# TIDA-010933-DCDC-Boost.net
KiCad netlist of a schematic drawn in Altium Designer
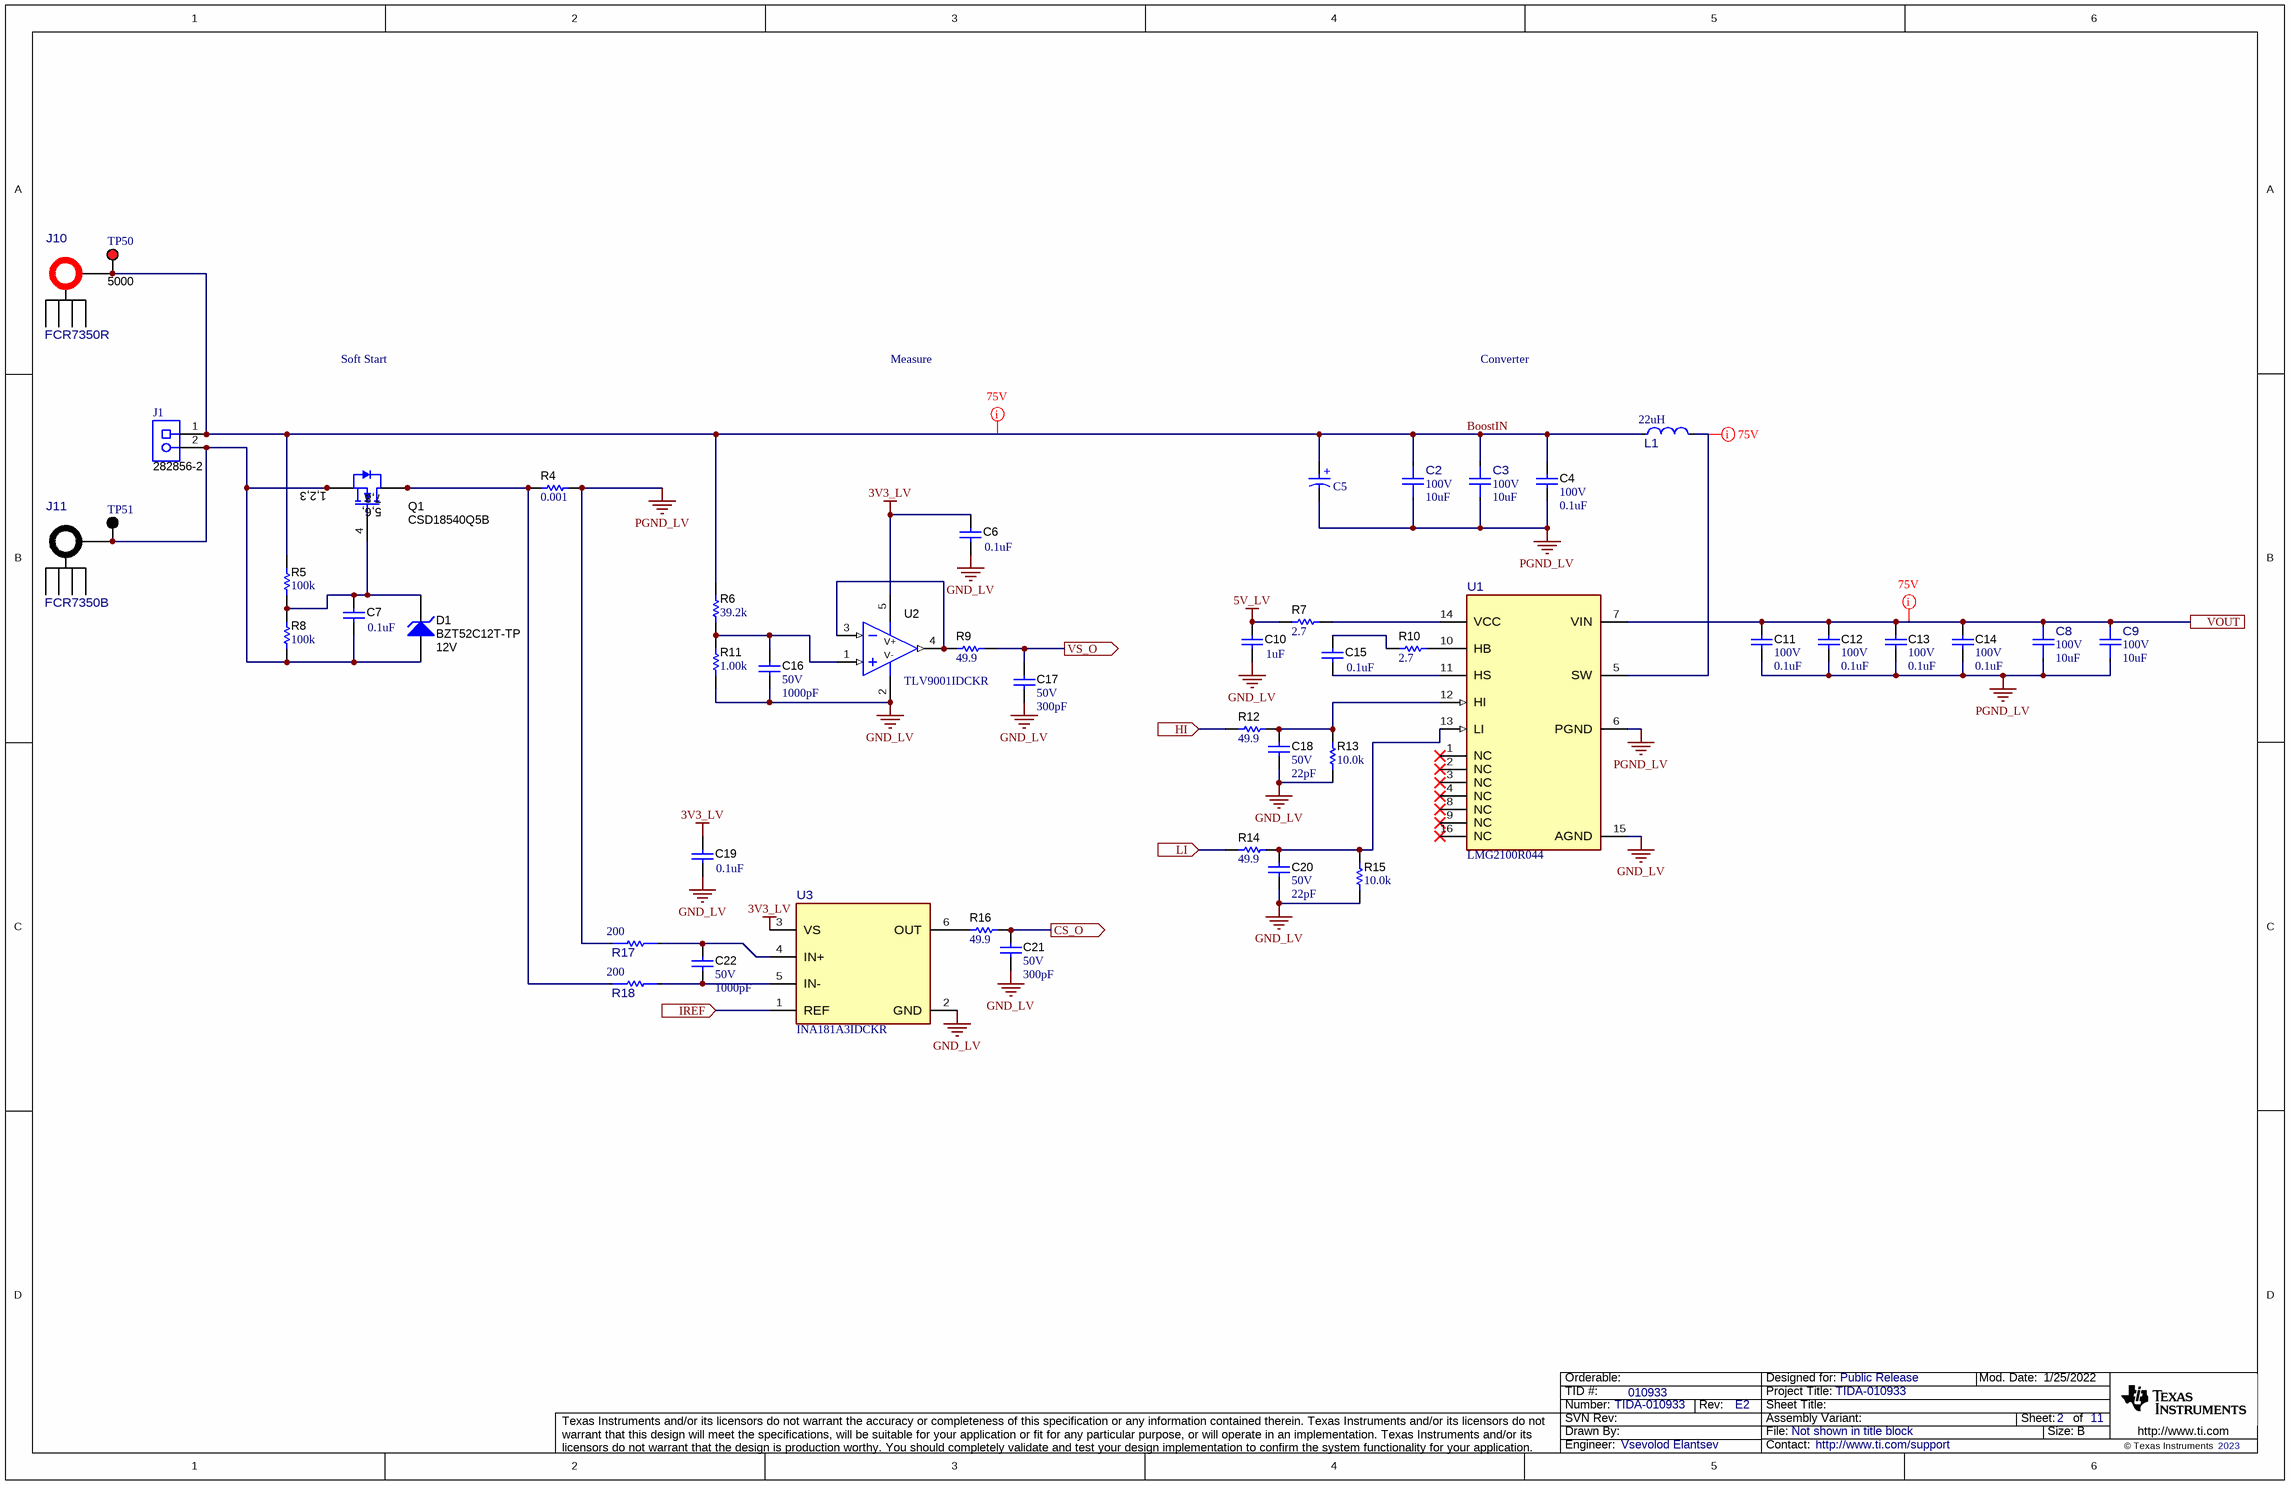
[diagram p0: TIDA-010933-DCDC-Boost.SchDoc]

(export (version "E")
  (design (tool "Eeschema 10.0.6"))
  (components
    (comp (ref "C2")
      (value "C3225X7R2A106K250AC")
      (footprint "FP-C3225X7R2A106K250AC_1210-MFG")
      (description "10 µF ±10% 100V Ceramic Capacitor X7R 1210 (3225 Metric)")
      (fields
        (field (name "DIGIKEY PART NUMBER") "445-C3225X7R2A106K250ACCT-ND")
        (field (name "MOUSER PART NUMBER") "810-C3225X7R2A106K25")
        (field (name "VDC_V") "100V")
        (field (name "VALUEDISPLAYED") "10uF")
      )
      (libsource (lib "Altium Vault - TI") (part "SYM-C3225X7R2A106K250AC"))
    )
    (comp (ref "C3")
      (value "C3225X7R2A106K250AC")
      (footprint "FP-C3225X7R2A106K250AC_1210-MFG")
      (description "10 µF ±10% 100V Ceramic Capacitor X7R 1210 (3225 Metric)")
      (fields
        (field (name "DIGIKEY PART NUMBER") "445-C3225X7R2A106K250ACCT-ND")
        (field (name "MOUSER PART NUMBER") "810-C3225X7R2A106K25")
        (field (name "VDC_V") "100V")
        (field (name "VALUEDISPLAYED") "10uF")
      )
      (libsource (lib "Altium Vault - TI") (part "SYM-C3225X7R2A106K250AC"))
    )
    (comp (ref "C4")
      (value "GRM155R62A104KE14D")
      (footprint "0402")
      (description "CAP, CERM, 0.1 uF, 100 V, +/- 10%, X5R, 0402")
      (fields
        (field (name "MANUFACTURER") "MuRata")
        (field (name "VDC_V") "100V")
        (field (name "VALUEDISPLAYED") "0.1uF")
        (field (name "PUBLISHER") "Texas Instruments")
      )
      (libsource (lib "Altium Vault - TI") (part "Capacitor"))
    )
    (comp (ref "C5")
      (value "860080775016")
      (footprint "WCAP-ATLI_D10H16")
      (description "WCAP-ATLI Aluminum Electrolytic Capacitor, Radial, THT, D10 x H16mm, 150µF, 63V")
      (fields (field (name "MANUFACTURER") "Wurth Elektronik"))
      (libsource (lib "Altium Vault - TI") (part "875585961005"))
    )
    (comp (ref "C6")
      (value "GRM155R71E104KE14D")
      (footprint "0402")
      (description "CAP, CERM, 0.1 uF, 25 V, +/- 10%, X7R, 0402")
      (fields
        (field (name "MANUFACTURER") "MuRata")
        (field (name "VALUEDISPLAYED") "0.1uF")
        (field (name "PUBLISHER") "Texas Instruments")
      )
      (libsource (lib "Altium Vault - TI") (part "Capacitor"))
    )
    (comp (ref "C7")
      (value "GRM155R71E104KE14D")
      (footprint "0402")
      (description "CAP, CERM, 0.1 uF, 25 V, +/- 10%, X7R, 0402")
      (fields
        (field (name "MANUFACTURER") "MuRata")
        (field (name "VALUEDISPLAYED") "0.1uF")
        (field (name "PUBLISHER") "Texas Instruments")
      )
      (libsource (lib "Altium Vault - TI") (part "Capacitor"))
    )
    (comp (ref "C8")
      (value "C3225X7R2A106K250AC")
      (footprint "FP-C3225X7R2A106K250AC_1210-MFG")
      (description "10 µF ±10% 100V Ceramic Capacitor X7R 1210 (3225 Metric)")
      (fields
        (field (name "DIGIKEY PART NUMBER") "445-C3225X7R2A106K250ACCT-ND")
        (field (name "MOUSER PART NUMBER") "810-C3225X7R2A106K25")
        (field (name "VDC_V") "100V")
        (field (name "VALUEDISPLAYED") "10uF")
      )
      (libsource (lib "Altium Vault - TI") (part "SYM-C3225X7R2A106K250AC"))
    )
    (comp (ref "C9")
      (value "C3225X7R2A106K250AC")
      (footprint "FP-C3225X7R2A106K250AC_1210-MFG")
      (description "10 µF ±10% 100V Ceramic Capacitor X7R 1210 (3225 Metric)")
      (fields
        (field (name "DIGIKEY PART NUMBER") "445-C3225X7R2A106K250ACCT-ND")
        (field (name "MOUSER PART NUMBER") "810-C3225X7R2A106K25")
        (field (name "VDC_V") "100V")
        (field (name "VALUEDISPLAYED") "10uF")
      )
      (libsource (lib "Altium Vault - TI") (part "SYM-C3225X7R2A106K250AC"))
    )
    (comp (ref "C10")
      (value "GRM155R61E105KA12D")
      (footprint "0402")
      (description "CAP, CERM, 1 uF, 25 V, +/- 10%, X5R, 0402")
      (fields
        (field (name "MANUFACTURER") "MuRata")
        (field (name "VALUEDISPLAYED") "1uF")
        (field (name "PUBLISHER") "Texas Instruments")
      )
      (libsource (lib "Altium Vault - TI") (part "Capacitor"))
    )
    (comp (ref "C11")
      (value "GRM155R62A104KE14D")
      (footprint "0402")
      (description "CAP, CERM, 0.1 uF, 100 V, +/- 10%, X5R, 0402")
      (fields
        (field (name "MANUFACTURER") "MuRata")
        (field (name "VDC_V") "100V")
        (field (name "VALUEDISPLAYED") "0.1uF")
        (field (name "PUBLISHER") "Texas Instruments")
      )
      (libsource (lib "Altium Vault - TI") (part "Capacitor"))
    )
    (comp (ref "C12")
      (value "GRM155R62A104KE14D")
      (footprint "0402")
      (description "CAP, CERM, 0.1 uF, 100 V, +/- 10%, X5R, 0402")
      (fields
        (field (name "MANUFACTURER") "MuRata")
        (field (name "VDC_V") "100V")
        (field (name "VALUEDISPLAYED") "0.1uF")
        (field (name "PUBLISHER") "Texas Instruments")
      )
      (libsource (lib "Altium Vault - TI") (part "Capacitor"))
    )
    (comp (ref "C13")
      (value "GRM155R62A104KE14D")
      (footprint "0402")
      (description "CAP, CERM, 0.1 uF, 100 V, +/- 10%, X5R, 0402")
      (fields
        (field (name "MANUFACTURER") "MuRata")
        (field (name "VDC_V") "100V")
        (field (name "VALUEDISPLAYED") "0.1uF")
        (field (name "PUBLISHER") "Texas Instruments")
      )
      (libsource (lib "Altium Vault - TI") (part "Capacitor"))
    )
    (comp (ref "C14")
      (value "GRM155R62A104KE14D")
      (footprint "0402")
      (description "CAP, CERM, 0.1 uF, 100 V, +/- 10%, X5R, 0402")
      (fields
        (field (name "MANUFACTURER") "MuRata")
        (field (name "VDC_V") "100V")
        (field (name "VALUEDISPLAYED") "0.1uF")
        (field (name "PUBLISHER") "Texas Instruments")
      )
      (libsource (lib "Altium Vault - TI") (part "Capacitor"))
    )
    (comp (ref "C15")
      (value "GRM155R71E104KE14D")
      (footprint "0402")
      (description "CAP, CERM, 0.1 uF, 25 V, +/- 10%, X7R, 0402")
      (fields
        (field (name "MANUFACTURER") "MuRata")
        (field (name "VALUEDISPLAYED") "0.1uF")
        (field (name "PUBLISHER") "Texas Instruments")
      )
      (libsource (lib "Altium Vault - TI") (part "Capacitor"))
    )
    (comp (ref "C16")
      (value "GRM1555C1H102JA01D")
      (footprint "0402")
      (description "CAP, CERM, 1000 pF, 50 V, +/- 5%, C0G/NP0, 0402")
      (fields
        (field (name "MANUFACTURER") "MuRata")
        (field (name "VDC_V") "50V")
        (field (name "VALUEDISPLAYED") "1000pF")
        (field (name "PUBLISHER") "Texas Instruments")
      )
      (libsource (lib "Altium Vault - TI") (part "Capacitor"))
    )
    (comp (ref "C17")
      (value "GRM1555C1H301JA01D")
      (footprint "0402")
      (description "CAP, CERM, 300 pF, 50 V, +/- 5%, C0G/NP0, 0402")
      (fields
        (field (name "MANUFACTURER") "MuRata")
        (field (name "VDC_V") "50V")
        (field (name "VALUEDISPLAYED") "300pF")
        (field (name "PUBLISHER") "Texas Instruments")
      )
      (libsource (lib "Altium Vault - TI") (part "Capacitor"))
    )
    (comp (ref "C18")
      (value "CC0402JRNPO9BN220")
      (footprint "0402")
      (description "CAP, CERM, 22 pF, 50 V,+/- 5%, C0G/NP0, 0402")
      (fields
        (field (name "VDC_V") "50V")
        (field (name "MANUFACTURER") "Yageo")
        (field (name "VALUEDISPLAYED") "22pF")
      )
      (libsource (lib "Altium Vault - TI") (part "Capacitor"))
    )
    (comp (ref "C19")
      (value "GRM155R71E104KE14D")
      (footprint "0402")
      (description "CAP, CERM, 0.1 uF, 25 V, +/- 10%, X7R, 0402")
      (fields
        (field (name "MANUFACTURER") "MuRata")
        (field (name "VALUEDISPLAYED") "0.1uF")
        (field (name "PUBLISHER") "Texas Instruments")
      )
      (libsource (lib "Altium Vault - TI") (part "Capacitor"))
    )
    (comp (ref "C20")
      (value "CC0402JRNPO9BN220")
      (footprint "0402")
      (description "CAP, CERM, 22 pF, 50 V,+/- 5%, C0G/NP0, 0402")
      (fields
        (field (name "VDC_V") "50V")
        (field (name "MANUFACTURER") "Yageo")
        (field (name "VALUEDISPLAYED") "22pF")
      )
      (libsource (lib "Altium Vault - TI") (part "Capacitor"))
    )
    (comp (ref "C21")
      (value "GRM1555C1H301JA01D")
      (footprint "0402")
      (description "CAP, CERM, 300 pF, 50 V, +/- 5%, C0G/NP0, 0402")
      (fields
        (field (name "MANUFACTURER") "MuRata")
        (field (name "VDC_V") "50V")
        (field (name "VALUEDISPLAYED") "300pF")
        (field (name "PUBLISHER") "Texas Instruments")
      )
      (libsource (lib "Altium Vault - TI") (part "Capacitor"))
    )
    (comp (ref "C22")
      (value "GRM1555C1H102JA01D")
      (footprint "0402")
      (description "CAP, CERM, 1000 pF, 50 V, +/- 5%, C0G/NP0, 0402")
      (fields
        (field (name "MANUFACTURER") "MuRata")
        (field (name "VDC_V") "50V")
        (field (name "VALUEDISPLAYED") "1000pF")
        (field (name "PUBLISHER") "Texas Instruments")
      )
      (libsource (lib "Altium Vault - TI") (part "Capacitor"))
    )
    (comp (ref "D1")
      (value "BZT52C12T-TP")
      (footprint "SOD-523")
      (description "Diode, Zener, 12 V, 200 mW, SOD-523")
      (fields (field (name "ALTIUM_VALUE") "12V") (field (name "MANUFACTURER") "Micro Commercial Components"))
      (libsource (lib "Altium Vault - TI") (part "Zener"))
    )
    (comp (ref "J1")
      (value "282856-2")
      (footprint "TE_282856-2")
      (description "Therminal Block, 5 mm, 2-pole, Tin, TH")
      (fields (field (name "MANUFACTURER") "TE Connectivity") (field (name "PUBLISHER") "Texas Instruments"))
      (libsource (lib "Altium Vault - TI") (part "Receptacle_2x1"))
    )
    (comp (ref "J10")
      (value "FCR7350R")
      (footprint "FP-FCR7350R_CONN_BANANA_JACK-MFG")
      (description "Banana Jack Connector Standard Banana Solder Red")
      (fields
        (field (name "MANUFACTURER") "CLIFF Electronic Components")
        (field (name "DIGIKEY PART NUMBER") "4654-FCR7350R-ND")
      )
      (libsource (lib "Altium Vault - TI") (part "SYM-FCR7350R"))
    )
    (comp (ref "J11")
      (value "FCR7350B")
      (footprint "FP-FCR7350B_CONN_BANANA_JACK-MFG")
      (description "Banana Jack Connector Standard Banana Solder Black")
      (fields
        (field (name "MANUFACTURER") "CLIFF Electronic Components")
        (field (name "DIGIKEY PART NUMBER") "4654-FCR7350B-ND")
      )
      (libsource (lib "Altium Vault - TI") (part "SYM-FCR7350B"))
    )
    (comp (ref "L1")
      (value "22uH")
      (footprint "FP-VER2923-223KL_PTH_INDUCTOR_26MM92_16MM46-MFG")
      (description "Shielded High Current Power Inductor, 22uH, 19A")
      (fields (field (name "MANUFACTURER") "Coilcraft") (field (name "PARTNUMBER") "VER2923-223KL"))
      (libsource (lib "Altium Vault - TI") (part "SYM-VER2923-223KL"))
    )
    (comp (ref "Q1")
      (value "CSD18540Q5B")
      (footprint "DNK0008A")
      (description "MOSFET, N-CH, 60 V, 100 A, DNK0008A (VSON-CLIP-8)")
      (fields (field (name "MANUFACTURER") "Texas Instruments"))
      (libsource (lib "Altium Vault - TI") (part "MOSFET_N_D56789G4S123"))
    )
    (comp (ref "R4")
      (value "CRF1206-FZ-R001ELF")
      (footprint "1206")
      (description "RES, 0.001, 1%, 1 W, AEC-Q200 Grade 0, 1206")
      (fields (field (name "MANUFACTURER") "Bourns") (field (name "VALUEDISPLAYED") "0.001"))
      (libsource (lib "Altium Vault - TI") (part "Resistor"))
    )
    (comp (ref "R5")
      (value "RC0603FR-07100KL")
      (footprint "0603")
      (description "RES, 100 k, 1%, 0.1 W, 0603")
      (fields (field (name "MANUFACTURER") "Yageo") (field (name "VALUEDISPLAYED") "100k"))
      (libsource (lib "Altium Vault - TI") (part "Resistor"))
    )
    (comp (ref "R6")
      (value "RT0603BRD0739K2L")
      (footprint "0603")
      (description "RES, 39.2 k, 0.1%, 0.1 W, 0603")
      (fields
        (field (name "MANUFACTURER") "Yageo America")
        (field (name "VALUEDISPLAYED") "39.2k")
        (field (name "PUBLISHER") "Texas Instruments")
      )
      (libsource (lib "Altium Vault - TI") (part "Resistor"))
    )
    (comp (ref "R7")
      (value "CRCW04022R70JNED")
      (footprint "0402")
      (description "RES, 2.7, 5%, 0.063 W, AEC-Q200 Grade 0, 0402")
      (fields (field (name "MANUFACTURER") "Vishay-Dale") (field (name "VALUEDISPLAYED") "2.7"))
      (libsource (lib "Altium Vault - TI") (part "Resistor"))
    )
    (comp (ref "R8")
      (value "RC0402FR-07100KL")
      (footprint "0402")
      (description "RES, 100 k, 1%, 0.0625 W, 0402")
      (fields
        (field (name "MANUFACTURER") "Yageo America")
        (field (name "VALUEDISPLAYED") "100k")
        (field (name "PUBLISHER") "Texas Instruments")
      )
      (libsource (lib "Altium Vault - TI") (part "Resistor"))
    )
    (comp (ref "R9")
      (value "RC0402FR-0749R9L")
      (footprint "0402")
      (description "RES, 49.9, 1%, 0.063 W, 0402")
      (fields
        (field (name "MANUFACTURER") "Yageo America")
        (field (name "VALUEDISPLAYED") "49.9")
        (field (name "PUBLISHER") "Texas Instruments")
      )
      (libsource (lib "Altium Vault - TI") (part "Resistor"))
    )
    (comp (ref "R10")
      (value "CRCW04022R70JNED")
      (footprint "0402")
      (description "RES, 2.7, 5%, 0.063 W, AEC-Q200 Grade 0, 0402")
      (fields (field (name "MANUFACTURER") "Vishay-Dale") (field (name "VALUEDISPLAYED") "2.7"))
      (libsource (lib "Altium Vault - TI") (part "Resistor"))
    )
    (comp (ref "R11")
      (value "ERA-2AEB102X")
      (footprint "0402")
      (description "RES, 1.00 k, 0.1%, 0.063 W, 0402")
      (fields
        (field (name "MANUFACTURER") "Panasonic")
        (field (name "VALUEDISPLAYED") "1.00k")
        (field (name "PUBLISHER") "Texas Instruments")
      )
      (libsource (lib "Altium Vault - TI") (part "Resistor"))
    )
    (comp (ref "R12")
      (value "RC0402FR-0749R9L")
      (footprint "0402")
      (description "RES, 49.9, 1%, 0.063 W, 0402")
      (fields
        (field (name "MANUFACTURER") "Yageo America")
        (field (name "VALUEDISPLAYED") "49.9")
        (field (name "PUBLISHER") "Texas Instruments")
      )
      (libsource (lib "Altium Vault - TI") (part "Resistor"))
    )
    (comp (ref "R13")
      (value "RC0402FR-0710KL")
      (footprint "0402")
      (description "RES, 10.0 k, 1%, 0.063 W, 0402")
      (fields (field (name "MANUFACTURER") "Yageo America") (field (name "VALUEDISPLAYED") "10.0k"))
      (libsource (lib "Altium Vault - TI") (part "Resistor"))
    )
    (comp (ref "R14")
      (value "RC0402FR-0749R9L")
      (footprint "0402")
      (description "RES, 49.9, 1%, 0.063 W, 0402")
      (fields
        (field (name "MANUFACTURER") "Yageo America")
        (field (name "VALUEDISPLAYED") "49.9")
        (field (name "PUBLISHER") "Texas Instruments")
      )
      (libsource (lib "Altium Vault - TI") (part "Resistor"))
    )
    (comp (ref "R15")
      (value "RC0402FR-0710KL")
      (footprint "0402")
      (description "RES, 10.0 k, 1%, 0.063 W, 0402")
      (fields (field (name "MANUFACTURER") "Yageo America") (field (name "VALUEDISPLAYED") "10.0k"))
      (libsource (lib "Altium Vault - TI") (part "Resistor"))
    )
    (comp (ref "R16")
      (value "RC0402FR-0749R9L")
      (footprint "0402")
      (description "RES, 49.9, 1%, 0.063 W, 0402")
      (fields
        (field (name "MANUFACTURER") "Yageo America")
        (field (name "VALUEDISPLAYED") "49.9")
        (field (name "PUBLISHER") "Texas Instruments")
      )
      (libsource (lib "Altium Vault - TI") (part "Resistor"))
    )
    (comp (ref "R17")
      (value "200")
      (footprint "FP-RC0402JR-07200RL_0402-MFG")
      (description "200 Ohms ±5% 0.063W, 1/16W Chip Resistor 0402 (1005 Metric) Moisture Resistant Thick Film")
      (fields
        (field (name "PART NUMBER") "RC0402JR-07200RL")
        (field (name "MOUSER PART NUMBER") "603-RC0402JR-07200RL")
      )
      (libsource (lib "Altium Vault - TI") (part "SYM-RC0402JR-07200RL"))
    )
    (comp (ref "R18")
      (value "200")
      (footprint "FP-RC0402JR-07200RL_0402-MFG")
      (description "200 Ohms ±5% 0.063W, 1/16W Chip Resistor 0402 (1005 Metric) Moisture Resistant Thick Film")
      (fields
        (field (name "PART NUMBER") "RC0402JR-07200RL")
        (field (name "MOUSER PART NUMBER") "603-RC0402JR-07200RL")
      )
      (libsource (lib "Altium Vault - TI") (part "SYM-RC0402JR-07200RL"))
    )
    (comp (ref "TP50")
      (value "5000")
      (footprint "Keystone5000")
      (description "Test Point, Miniature, Red, TH")
      (fields
        (field (name "MANUFACTURER") "Keystone Electronics")
        (field (name "PUBLISHER") "Texas Instruments")
      )
      (libsource (lib "Altium Vault - TI") (part "5000"))
    )
    (comp (ref "TP51")
      (value "5001")
      (footprint "Keystone5001")
      (description "Test Point, Miniature, Black, TH")
      (fields
        (field (name "MANUFACTURER") "Keystone Electronics")
        (field (name "PUBLISHER") "Texas Instruments")
      )
      (libsource (lib "Altium Vault - TI") (part "5001"))
    )
    (comp (ref "U1")
      (value "LMG2100R044")
      (footprint "VBN0016A-MFG")
      (description "100-V, 53-A GaN Half-Bridge Power Stage")
      (fields (field (name "MANUFACTURER") "Texas Instruments") (field (name "PARTNUMBER") "LMG2100R044"))
      (libsource (lib "Altium Vault - TI") (part "SYM-LMG2100R026"))
    )
    (comp (ref "U2")
      (value "TLV9001IDCKR")
      (footprint "DCK0005A_N")
      (description "Low-Power, Rail-to-Rail In and Out, 1-MHz Operational Amplifier, DCK0005A (SOT-SC70-5)")
      (fields
        (field (name "ALTERNATE PARTNUMBER") "TLV9001IDCKT")
        (field (name "MANUFACTURER") "Texas Instruments")
        (field (name "PARTNUMBER") "TLV9001IDCKR")
      )
      (libsource (lib "Altium Vault - TI") (part "OPAMP_SINGLE_SOT321"))
    )
    (comp (ref "U3")
      (value "INA181A3IDCKR")
      (footprint "DCK0006A-MFG")
      (description "Bidirectional, Low- and High-Side Voltage Output, Current-Sense Amplifiers")
      (fields
        (field (name "MANUFACTURER") "Texas Instruments")
        (field (name "PARTNUMBER") "INA181A3IDCKR")
        (field (name "DIGIKEY PART NUMBER") "296-INA181A3IDCKRTR-ND")
      )
      (libsource (lib "Altium Vault - TI") (part "SYM-INA181A3IDCKR"))
    )
  )
  (nets
    (net (code "1") (name "/BoostIN") (class "Default")
      (node (ref "C2") (pin "2") (pinfunction "2_2") (pintype "passive"))
      (node (ref "C3") (pin "2") (pinfunction "2_2") (pintype "passive"))
      (node (ref "C4") (pin "1") (pinfunction "1_1") (pintype "passive"))
      (node (ref "C5") (pin "1") (pinfunction "P_1") (pintype "passive"))
      (node (ref "J1") (pin "1") (pinfunction "1_1") (pintype "passive"))
      (node (ref "J10") (pin "1") (pinfunction "1_1") (pintype "passive"))
      (node (ref "L1") (pin "1") (pinfunction "1_1") (pintype "passive"))
      (node (ref "R5") (pin "2") (pinfunction "2_2") (pintype "passive"))
      (node (ref "R6") (pin "2") (pinfunction "2_2") (pintype "passive"))
      (node (ref "TP50") (pin "1") (pintype "passive"))
    )
    (net (code "2") (name "/CS_O") (class "Default")
      (node (ref "C21") (pin "1") (pinfunction "1_1") (pintype "passive"))
      (node (ref "R16") (pin "2") (pinfunction "2_2") (pintype "passive"))
    )
    (net (code "3") (name "/HI") (class "Default")
      (node (ref "R12") (pin "1") (pinfunction "1_1") (pintype "passive"))
    )
    (net (code "4") (name "/IREF") (class "Default")
      (node (ref "U3") (pin "1") (pinfunction "REF_1") (pintype "passive"))
    )
    (net (code "5") (name "/LI") (class "Default")
      (node (ref "R14") (pin "1") (pinfunction "1_1") (pintype "passive"))
    )
    (net (code "6") (name "/VOUT") (class "Default")
      (node (ref "C11") (pin "1") (pinfunction "1_1") (pintype "passive"))
      (node (ref "C12") (pin "1") (pinfunction "1_1") (pintype "passive"))
      (node (ref "C13") (pin "1") (pinfunction "1_1") (pintype "passive"))
      (node (ref "C14") (pin "1") (pinfunction "1_1") (pintype "passive"))
      (node (ref "C8") (pin "2") (pinfunction "2_2") (pintype "passive"))
      (node (ref "C9") (pin "2") (pinfunction "2_2") (pintype "passive"))
      (node (ref "U1") (pin "7") (pinfunction "VIN_7") (pintype "power_in"))
    )
    (net (code "7") (name "/VS_O") (class "Default")
      (node (ref "C17") (pin "1") (pinfunction "1_1") (pintype "passive"))
      (node (ref "R9") (pin "2") (pinfunction "2_2") (pintype "passive"))
    )
    (net (code "8") (name "3V3_LV") (class "Default")
      (node (ref "C19") (pin "1") (pinfunction "1_1") (pintype "passive"))
      (node (ref "C6") (pin "1") (pinfunction "1_1") (pintype "passive"))
      (node (ref "U2") (pin "5") (pinfunction "V+_5") (pintype "power_in"))
      (node (ref "U3") (pin "3") (pinfunction "VS_3") (pintype "power_in"))
    )
    (net (code "9") (name "5V_LV") (class "Default")
      (node (ref "C10") (pin "1") (pinfunction "1_1") (pintype "passive"))
      (node (ref "R7") (pin "1") (pinfunction "1_1") (pintype "passive"))
    )
    (net (code "10") (name "GND_LV") (class "Default")
      (node (ref "C10") (pin "2") (pinfunction "2_2") (pintype "passive"))
      (node (ref "C16") (pin "2") (pinfunction "2_2") (pintype "passive"))
      (node (ref "C17") (pin "2") (pinfunction "2_2") (pintype "passive"))
      (node (ref "C18") (pin "2") (pinfunction "2_2") (pintype "passive"))
      (node (ref "C19") (pin "2") (pinfunction "2_2") (pintype "passive"))
      (node (ref "C20") (pin "2") (pinfunction "2_2") (pintype "passive"))
      (node (ref "C21") (pin "2") (pinfunction "2_2") (pintype "passive"))
      (node (ref "C6") (pin "2") (pinfunction "2_2") (pintype "passive"))
      (node (ref "R11") (pin "1") (pinfunction "1_1") (pintype "passive"))
      (node (ref "R13") (pin "1") (pinfunction "1_1") (pintype "passive"))
      (node (ref "R15") (pin "1") (pinfunction "1_1") (pintype "passive"))
      (node (ref "U1") (pin "15") (pinfunction "AGND_15") (pintype "power_in"))
      (node (ref "U2") (pin "2") (pinfunction "V-_2") (pintype "power_in"))
      (node (ref "U3") (pin "2") (pinfunction "GND_2") (pintype "power_in"))
    )
    (net (code "11") (name "Net-(C15-Pad1)") (class "Default")
      (node (ref "C15") (pin "1") (pinfunction "1_1") (pintype "passive"))
      (node (ref "R10") (pin "1") (pinfunction "1_1") (pintype "passive"))
    )
    (net (code "12") (name "Net-(D1-A)") (class "Default")
      (node (ref "C7") (pin "2") (pinfunction "2_2") (pintype "passive"))
      (node (ref "D1") (pin "2") (pinfunction "A_2") (pintype "passive"))
      (node (ref "J1") (pin "2") (pinfunction "2_2") (pintype "passive"))
      (node (ref "J11") (pin "1") (pinfunction "1_1") (pintype "passive"))
      (node (ref "Q1") (pin "1") (pinfunction "S_1") (pintype "passive"))
      (node (ref "Q1") (pin "2") (pinfunction "S_2") (pintype "passive"))
      (node (ref "Q1") (pin "3") (pinfunction "S_3") (pintype "passive"))
      (node (ref "R8") (pin "1") (pinfunction "1_1") (pintype "passive"))
      (node (ref "TP51") (pin "1") (pintype "passive"))
    )
    (net (code "13") (name "Net-(D1-K)") (class "Default")
      (node (ref "C7") (pin "1") (pinfunction "1_1") (pintype "passive"))
      (node (ref "D1") (pin "1") (pinfunction "K_1") (pintype "passive"))
      (node (ref "Q1") (pin "4") (pinfunction "G_4") (pintype "passive"))
      (node (ref "R5") (pin "1") (pinfunction "1_1") (pintype "passive"))
      (node (ref "R8") (pin "2") (pinfunction "2_2") (pintype "passive"))
    )
    (net (code "14") (name "Net-(Q1-D-Pad5)") (class "Default")
      (node (ref "Q1") (pin "5") (pinfunction "D_5") (pintype "passive"))
      (node (ref "Q1") (pin "6") (pinfunction "D_6") (pintype "passive"))
      (node (ref "Q1") (pin "7") (pinfunction "D_7") (pintype "passive"))
      (node (ref "Q1") (pin "8") (pinfunction "D_8") (pintype "passive"))
      (node (ref "Q1") (pin "9") (pinfunction "D_9") (pintype "passive"))
      (node (ref "R18") (pin "1") (pinfunction "1_1") (pintype "passive"))
      (node (ref "R4") (pin "1") (pinfunction "1_1") (pintype "passive"))
    )
    (net (code "15") (name "Net-(U1-HB)") (class "Default")
      (node (ref "R10") (pin "2") (pinfunction "2_2") (pintype "passive"))
      (node (ref "U1") (pin "10") (pinfunction "HB_10") (pintype "power_in"))
    )
    (net (code "16") (name "Net-(U1-HI)") (class "Default")
      (node (ref "C18") (pin "1") (pinfunction "1_1") (pintype "passive"))
      (node (ref "R12") (pin "2") (pinfunction "2_2") (pintype "passive"))
      (node (ref "R13") (pin "2") (pinfunction "2_2") (pintype "passive"))
      (node (ref "U1") (pin "12") (pinfunction "HI_12") (pintype "input"))
    )
    (net (code "17") (name "Net-(U1-HS)") (class "Default")
      (node (ref "C15") (pin "2") (pinfunction "2_2") (pintype "passive"))
      (node (ref "U1") (pin "11") (pinfunction "HS_11") (pintype "power_in"))
    )
    (net (code "18") (name "Net-(U1-LI)") (class "Default")
      (node (ref "C20") (pin "1") (pinfunction "1_1") (pintype "passive"))
      (node (ref "R14") (pin "2") (pinfunction "2_2") (pintype "passive"))
      (node (ref "R15") (pin "2") (pinfunction "2_2") (pintype "passive"))
      (node (ref "U1") (pin "13") (pinfunction "LI_13") (pintype "input"))
    )
    (net (code "19") (name "Net-(U1-SW)") (class "Default")
      (node (ref "L1") (pin "2") (pinfunction "2_2") (pintype "passive"))
      (node (ref "U1") (pin "5") (pinfunction "SW_5") (pintype "power_in"))
    )
    (net (code "20") (name "Net-(U1-VCC)") (class "Default")
      (node (ref "R7") (pin "2") (pinfunction "2_2") (pintype "passive"))
      (node (ref "U1") (pin "14") (pinfunction "VCC_14") (pintype "power_in"))
    )
    (net (code "21") (name "Net-(U2-IN+)") (class "Default")
      (node (ref "C16") (pin "1") (pinfunction "1_1") (pintype "passive"))
      (node (ref "R11") (pin "2") (pinfunction "2_2") (pintype "passive"))
      (node (ref "R6") (pin "1") (pinfunction "1_1") (pintype "passive"))
      (node (ref "U2") (pin "1") (pinfunction "IN+_1") (pintype "input"))
    )
    (net (code "22") (name "Net-(U2-IN-)") (class "Default")
      (node (ref "R9") (pin "1") (pinfunction "1_1") (pintype "passive"))
      (node (ref "U2") (pin "3") (pinfunction "IN-_3") (pintype "input"))
      (node (ref "U2") (pin "4") (pinfunction "OUT_4") (pintype "output"))
    )
    (net (code "23") (name "Net-(U3-IN+)") (class "Default")
      (node (ref "C22") (pin "1") (pinfunction "1_1") (pintype "passive"))
      (node (ref "R17") (pin "2") (pinfunction "2_2") (pintype "passive"))
      (node (ref "U3") (pin "4") (pinfunction "IN+_4") (pintype "tri_state"))
    )
    (net (code "24") (name "Net-(U3-IN-)") (class "Default")
      (node (ref "C22") (pin "2") (pinfunction "2_2") (pintype "passive"))
      (node (ref "R18") (pin "2") (pinfunction "2_2") (pintype "passive"))
      (node (ref "U3") (pin "5") (pinfunction "IN-_5") (pintype "tri_state"))
    )
    (net (code "25") (name "Net-(U3-OUT)") (class "Default")
      (node (ref "R16") (pin "1") (pinfunction "1_1") (pintype "passive"))
      (node (ref "U3") (pin "6") (pinfunction "OUT_6") (pintype "passive"))
    )
    (net (code "26") (name "PGND_LV") (class "Default")
      (node (ref "C11") (pin "2") (pinfunction "2_2") (pintype "passive"))
      (node (ref "C12") (pin "2") (pinfunction "2_2") (pintype "passive"))
      (node (ref "C13") (pin "2") (pinfunction "2_2") (pintype "passive"))
      (node (ref "C14") (pin "2") (pinfunction "2_2") (pintype "passive"))
      (node (ref "C2") (pin "1") (pinfunction "1_1") (pintype "passive"))
      (node (ref "C3") (pin "1") (pinfunction "1_1") (pintype "passive"))
      (node (ref "C4") (pin "2") (pinfunction "2_2") (pintype "passive"))
      (node (ref "C5") (pin "2") (pinfunction "N_2") (pintype "passive"))
      (node (ref "C8") (pin "1") (pinfunction "1_1") (pintype "passive"))
      (node (ref "C9") (pin "1") (pinfunction "1_1") (pintype "passive"))
      (node (ref "R17") (pin "1") (pinfunction "1_1") (pintype "passive"))
      (node (ref "R4") (pin "2") (pinfunction "2_2") (pintype "passive"))
      (node (ref "U1") (pin "6") (pinfunction "PGND_6") (pintype "power_in"))
    )
    (net (code "27") (name "unconnected-(J10-MNT_1-Pad2)") (class "Default")
      (node (ref "J10") (pin "2") (pinfunction "MNT_1_2") (pintype "passive"))
    )
    (net (code "28") (name "unconnected-(J10-MNT_2-Pad3)") (class "Default")
      (node (ref "J10") (pin "3") (pinfunction "MNT_2_3") (pintype "passive"))
    )
    (net (code "29") (name "unconnected-(J10-MNT_3-Pad4)") (class "Default")
      (node (ref "J10") (pin "4") (pinfunction "MNT_3_4") (pintype "passive"))
    )
    (net (code "30") (name "unconnected-(J10-MNT_4-Pad5)") (class "Default")
      (node (ref "J10") (pin "5") (pinfunction "MNT_4_5") (pintype "passive"))
    )
    (net (code "31") (name "unconnected-(J11-MNT_1-Pad2)") (class "Default")
      (node (ref "J11") (pin "2") (pinfunction "MNT_1_2") (pintype "passive"))
    )
    (net (code "32") (name "unconnected-(J11-MNT_2-Pad3)") (class "Default")
      (node (ref "J11") (pin "3") (pinfunction "MNT_2_3") (pintype "passive"))
    )
    (net (code "33") (name "unconnected-(J11-MNT_3-Pad4)") (class "Default")
      (node (ref "J11") (pin "4") (pinfunction "MNT_3_4") (pintype "passive"))
    )
    (net (code "34") (name "unconnected-(J11-MNT_4-Pad5)") (class "Default")
      (node (ref "J11") (pin "5") (pinfunction "MNT_4_5") (pintype "passive"))
    )
    (net (code "35") (name "unconnected-(U1-NC-Pad1)") (class "Default")
      (node (ref "U1") (pin "1") (pinfunction "NC_1") (pintype "passive+no_connect"))
    )
    (net (code "36") (name "unconnected-(U1-NC-Pad2)") (class "Default")
      (node (ref "U1") (pin "2") (pinfunction "NC_2") (pintype "passive+no_connect"))
    )
    (net (code "37") (name "unconnected-(U1-NC-Pad3)") (class "Default")
      (node (ref "U1") (pin "3") (pinfunction "NC_3") (pintype "passive+no_connect"))
    )
    (net (code "38") (name "unconnected-(U1-NC-Pad4)") (class "Default")
      (node (ref "U1") (pin "4") (pinfunction "NC_4") (pintype "passive+no_connect"))
    )
    (net (code "39") (name "unconnected-(U1-NC-Pad8)") (class "Default")
      (node (ref "U1") (pin "8") (pinfunction "NC_8") (pintype "passive+no_connect"))
    )
    (net (code "40") (name "unconnected-(U1-NC-Pad9)") (class "Default")
      (node (ref "U1") (pin "9") (pinfunction "NC_9") (pintype "passive+no_connect"))
    )
    (net (code "41") (name "unconnected-(U1-NC-Pad16)") (class "Default")
      (node (ref "U1") (pin "16") (pinfunction "NC_16") (pintype "passive+no_connect"))
    )
  )
)
